# CheetahBooster.net
KiCad netlist of a schematic drawn in EAGLE
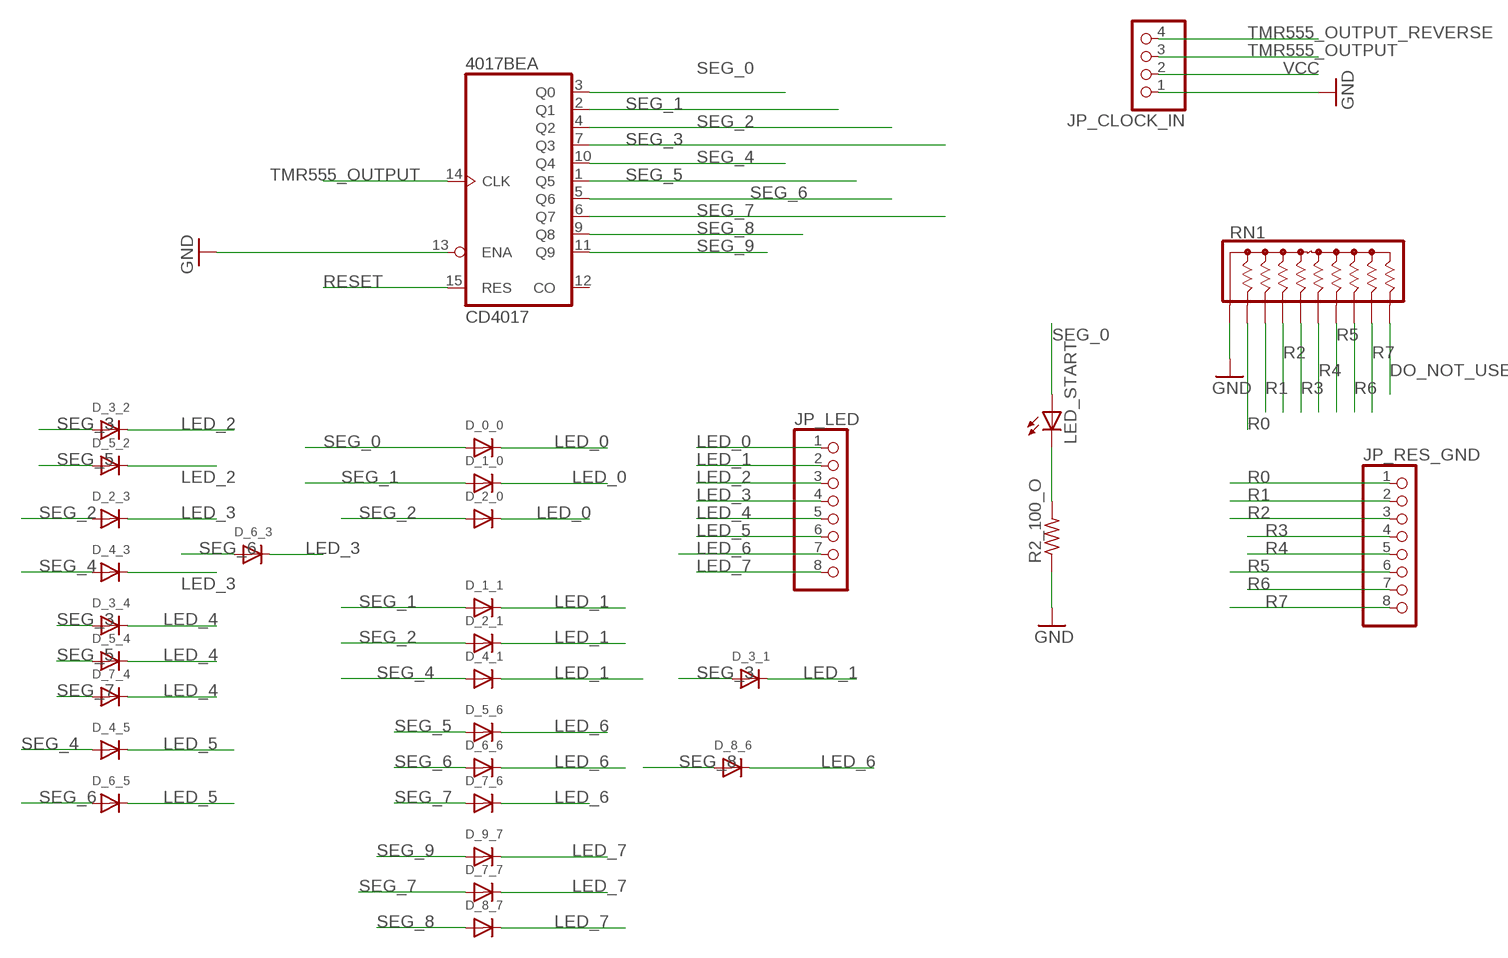
[diagram p0: schematic, sheet 1]

(export (version "E")
  (design (tool "Eeschema 10.0.6"))
  (components
    (comp (ref "4017BE")
      (value "CD4017")
      (footprint "eagle-import:DIL16")
      (libsource (lib "eagle-import") (part "CD4017"))
    )
    (comp (ref "D_0_0")
      (value "DIODESMA")
      (footprint "eagle-import:SMADIODE")
      (libsource (lib "eagle-import") (part "DIODESMA"))
    )
    (comp (ref "D_1_0")
      (value "DIODESMA")
      (footprint "eagle-import:SMADIODE")
      (libsource (lib "eagle-import") (part "DIODESMA"))
    )
    (comp (ref "D_1_1")
      (value "DIODESMA")
      (footprint "eagle-import:SMADIODE")
      (libsource (lib "eagle-import") (part "DIODESMA"))
    )
    (comp (ref "D_2_0")
      (value "DIODESMA")
      (footprint "eagle-import:SMADIODE")
      (libsource (lib "eagle-import") (part "DIODESMA"))
    )
    (comp (ref "D_2_1")
      (value "DIODESMA")
      (footprint "eagle-import:SMADIODE")
      (libsource (lib "eagle-import") (part "DIODESMA"))
    )
    (comp (ref "D_2_3")
      (value "DIODESMA")
      (footprint "eagle-import:SMADIODE")
      (libsource (lib "eagle-import") (part "DIODESMA"))
    )
    (comp (ref "D_3_1")
      (value "DIODESMA")
      (footprint "eagle-import:SMADIODE")
      (libsource (lib "eagle-import") (part "DIODESMA"))
    )
    (comp (ref "D_3_2")
      (value "DIODESMA")
      (footprint "eagle-import:SMADIODE")
      (libsource (lib "eagle-import") (part "DIODESMA"))
    )
    (comp (ref "D_3_4")
      (value "DIODESMA")
      (footprint "eagle-import:SMADIODE")
      (libsource (lib "eagle-import") (part "DIODESMA"))
    )
    (comp (ref "D_4_1")
      (value "DIODESMA")
      (footprint "eagle-import:SMADIODE")
      (libsource (lib "eagle-import") (part "DIODESMA"))
    )
    (comp (ref "D_4_3")
      (value "DIODESMA")
      (footprint "eagle-import:SMADIODE")
      (libsource (lib "eagle-import") (part "DIODESMA"))
    )
    (comp (ref "D_4_5")
      (value "DIODESMA")
      (footprint "eagle-import:SMADIODE")
      (libsource (lib "eagle-import") (part "DIODESMA"))
    )
    (comp (ref "D_5_2")
      (value "DIODESMA")
      (footprint "eagle-import:SMADIODE")
      (libsource (lib "eagle-import") (part "DIODESMA"))
    )
    (comp (ref "D_5_4")
      (value "DIODESMA")
      (footprint "eagle-import:SMADIODE")
      (libsource (lib "eagle-import") (part "DIODESMA"))
    )
    (comp (ref "D_5_6")
      (value "DIODESMA")
      (footprint "eagle-import:SMADIODE")
      (libsource (lib "eagle-import") (part "DIODESMA"))
    )
    (comp (ref "D_6_3")
      (value "DIODESMA")
      (footprint "eagle-import:SMADIODE")
      (libsource (lib "eagle-import") (part "DIODESMA"))
    )
    (comp (ref "D_6_5")
      (value "DIODESMA")
      (footprint "eagle-import:SMADIODE")
      (libsource (lib "eagle-import") (part "DIODESMA"))
    )
    (comp (ref "D_6_6")
      (value "DIODESMA")
      (footprint "eagle-import:SMADIODE")
      (libsource (lib "eagle-import") (part "DIODESMA"))
    )
    (comp (ref "D_7_4")
      (value "DIODESMA")
      (footprint "eagle-import:SMADIODE")
      (libsource (lib "eagle-import") (part "DIODESMA"))
    )
    (comp (ref "D_7_6")
      (value "DIODESMA")
      (footprint "eagle-import:SMADIODE")
      (libsource (lib "eagle-import") (part "DIODESMA"))
    )
    (comp (ref "D_7_7")
      (value "DIODESMA")
      (footprint "eagle-import:SMADIODE")
      (libsource (lib "eagle-import") (part "DIODESMA"))
    )
    (comp (ref "D_8_6")
      (value "DIODESMA")
      (footprint "eagle-import:SMADIODE")
      (libsource (lib "eagle-import") (part "DIODESMA"))
    )
    (comp (ref "D_8_7")
      (value "DIODESMA")
      (footprint "eagle-import:SMADIODE")
      (libsource (lib "eagle-import") (part "DIODESMA"))
    )
    (comp (ref "D_9_7")
      (value "DIODESMA")
      (footprint "eagle-import:SMADIODE")
      (libsource (lib "eagle-import") (part "DIODESMA"))
    )
    (comp (ref "JP_CLOCK_IN")
      (value "PINHD-1X4")
      (footprint "eagle-import:1X04")
      (libsource (lib "eagle-import") (part "PINHD-1X4"))
    )
    (comp (ref "JP_LED")
      (value "PINHD-1X8")
      (footprint "eagle-import:1X08")
      (libsource (lib "eagle-import") (part "PINHD-1X8"))
    )
    (comp (ref "JP_RES_GND")
      (value "PINHD-1X8")
      (footprint "eagle-import:1X08")
      (libsource (lib "eagle-import") (part "PINHD-1X8"))
    )
    (comp (ref "LED_START")
      (value "LEDSMT1206")
      (footprint "eagle-import:1206")
      (libsource (lib "eagle-import") (part "LEDSMT1206"))
    )
    (comp (ref "R2_100_O")
      (value "R-US_R1206")
      (footprint "eagle-import:R1206")
      (libsource (lib "eagle-import") (part "R-US_R1206"))
    )
    (comp (ref "RN1")
      (value "4610X")
      (footprint "eagle-import:SIP10")
      (libsource (lib "eagle-import") (part "4610X"))
    )
  )
  (nets
    (net (code "1") (name "/DO_NOT_USE") (class "Default")
      (node (ref "RN1") (pin "10") (pinfunction "10_10") (pintype "passive"))
    )
    (net (code "2") (name "/LED_0") (class "Default")
      (node (ref "D_0_0") (pin "C") (pinfunction "C_C") (pintype "passive"))
      (node (ref "D_1_0") (pin "C") (pinfunction "C_C") (pintype "passive"))
      (node (ref "D_2_0") (pin "C") (pinfunction "C_C") (pintype "passive"))
      (node (ref "JP_LED") (pin "1") (pinfunction "1_1") (pintype "passive"))
    )
    (net (code "3") (name "/LED_1") (class "Default")
      (node (ref "D_1_1") (pin "C") (pinfunction "C_C") (pintype "passive"))
      (node (ref "D_2_1") (pin "C") (pinfunction "C_C") (pintype "passive"))
      (node (ref "D_3_1") (pin "C") (pinfunction "C_C") (pintype "passive"))
      (node (ref "D_4_1") (pin "C") (pinfunction "C_C") (pintype "passive"))
      (node (ref "JP_LED") (pin "2") (pinfunction "2_2") (pintype "passive"))
    )
    (net (code "4") (name "/LED_2") (class "Default")
      (node (ref "D_3_2") (pin "C") (pinfunction "C_C") (pintype "passive"))
      (node (ref "D_5_2") (pin "C") (pinfunction "C_C") (pintype "passive"))
      (node (ref "JP_LED") (pin "3") (pinfunction "3_3") (pintype "passive"))
    )
    (net (code "5") (name "/LED_3") (class "Default")
      (node (ref "D_2_3") (pin "C") (pinfunction "C_C") (pintype "passive"))
      (node (ref "D_4_3") (pin "C") (pinfunction "C_C") (pintype "passive"))
      (node (ref "D_6_3") (pin "C") (pinfunction "C_C") (pintype "passive"))
      (node (ref "JP_LED") (pin "4") (pinfunction "4_4") (pintype "passive"))
    )
    (net (code "6") (name "/LED_4") (class "Default")
      (node (ref "D_3_4") (pin "C") (pinfunction "C_C") (pintype "passive"))
      (node (ref "D_5_4") (pin "C") (pinfunction "C_C") (pintype "passive"))
      (node (ref "D_7_4") (pin "C") (pinfunction "C_C") (pintype "passive"))
      (node (ref "JP_LED") (pin "5") (pinfunction "5_5") (pintype "passive"))
    )
    (net (code "7") (name "/LED_5") (class "Default")
      (node (ref "D_4_5") (pin "C") (pinfunction "C_C") (pintype "passive"))
      (node (ref "D_6_5") (pin "C") (pinfunction "C_C") (pintype "passive"))
      (node (ref "JP_LED") (pin "6") (pinfunction "6_6") (pintype "passive"))
    )
    (net (code "8") (name "/LED_6") (class "Default")
      (node (ref "D_5_6") (pin "C") (pinfunction "C_C") (pintype "passive"))
      (node (ref "D_6_6") (pin "C") (pinfunction "C_C") (pintype "passive"))
      (node (ref "D_7_6") (pin "C") (pinfunction "C_C") (pintype "passive"))
      (node (ref "D_8_6") (pin "C") (pinfunction "C_C") (pintype "passive"))
      (node (ref "JP_LED") (pin "7") (pinfunction "7_7") (pintype "passive"))
    )
    (net (code "9") (name "/LED_7") (class "Default")
      (node (ref "D_7_7") (pin "C") (pinfunction "C_C") (pintype "passive"))
      (node (ref "D_8_7") (pin "C") (pinfunction "C_C") (pintype "passive"))
      (node (ref "D_9_7") (pin "C") (pinfunction "C_C") (pintype "passive"))
      (node (ref "JP_LED") (pin "8") (pinfunction "8_8") (pintype "passive"))
    )
    (net (code "10") (name "/R0") (class "Default")
      (node (ref "JP_RES_GND") (pin "1") (pinfunction "1_1") (pintype "passive"))
      (node (ref "RN1") (pin "2") (pinfunction "2_2") (pintype "passive"))
    )
    (net (code "11") (name "/R1") (class "Default")
      (node (ref "JP_RES_GND") (pin "2") (pinfunction "2_2") (pintype "passive"))
      (node (ref "RN1") (pin "3") (pinfunction "3_3") (pintype "passive"))
    )
    (net (code "12") (name "/R2") (class "Default")
      (node (ref "JP_RES_GND") (pin "3") (pinfunction "3_3") (pintype "passive"))
      (node (ref "RN1") (pin "4") (pinfunction "4_4") (pintype "passive"))
    )
    (net (code "13") (name "/R3") (class "Default")
      (node (ref "JP_RES_GND") (pin "4") (pinfunction "4_4") (pintype "passive"))
      (node (ref "RN1") (pin "5") (pinfunction "5_5") (pintype "passive"))
    )
    (net (code "14") (name "/R4") (class "Default")
      (node (ref "JP_RES_GND") (pin "5") (pinfunction "5_5") (pintype "passive"))
      (node (ref "RN1") (pin "6") (pinfunction "6_6") (pintype "passive"))
    )
    (net (code "15") (name "/R5") (class "Default")
      (node (ref "JP_RES_GND") (pin "6") (pinfunction "6_6") (pintype "passive"))
      (node (ref "RN1") (pin "7") (pinfunction "7_7") (pintype "passive"))
    )
    (net (code "16") (name "/R6") (class "Default")
      (node (ref "JP_RES_GND") (pin "7") (pinfunction "7_7") (pintype "passive"))
      (node (ref "RN1") (pin "8") (pinfunction "8_8") (pintype "passive"))
    )
    (net (code "17") (name "/R7") (class "Default")
      (node (ref "JP_RES_GND") (pin "8") (pinfunction "8_8") (pintype "passive"))
      (node (ref "RN1") (pin "9") (pinfunction "9_9") (pintype "passive"))
    )
    (net (code "18") (name "/RESET") (class "Default")
      (node (ref "4017BE") (pin "15") (pinfunction "RES_15") (pintype "input"))
    )
    (net (code "19") (name "/SEG_0") (class "Default")
      (node (ref "4017BE") (pin "3") (pinfunction "Q0_3") (pintype "output"))
      (node (ref "D_0_0") (pin "A") (pinfunction "A_A") (pintype "passive"))
      (node (ref "LED_START") (pin "A") (pinfunction "A_A") (pintype "passive"))
    )
    (net (code "20") (name "/SEG_1") (class "Default")
      (node (ref "4017BE") (pin "2") (pinfunction "Q1_2") (pintype "output"))
      (node (ref "D_1_0") (pin "A") (pinfunction "A_A") (pintype "passive"))
      (node (ref "D_1_1") (pin "A") (pinfunction "A_A") (pintype "passive"))
    )
    (net (code "21") (name "/SEG_2") (class "Default")
      (node (ref "4017BE") (pin "4") (pinfunction "Q2_4") (pintype "output"))
      (node (ref "D_2_0") (pin "A") (pinfunction "A_A") (pintype "passive"))
      (node (ref "D_2_1") (pin "A") (pinfunction "A_A") (pintype "passive"))
      (node (ref "D_2_3") (pin "A") (pinfunction "A_A") (pintype "passive"))
    )
    (net (code "22") (name "/SEG_3") (class "Default")
      (node (ref "4017BE") (pin "7") (pinfunction "Q3_7") (pintype "output"))
      (node (ref "D_3_1") (pin "A") (pinfunction "A_A") (pintype "passive"))
      (node (ref "D_3_2") (pin "A") (pinfunction "A_A") (pintype "passive"))
      (node (ref "D_3_4") (pin "A") (pinfunction "A_A") (pintype "passive"))
    )
    (net (code "23") (name "/SEG_4") (class "Default")
      (node (ref "4017BE") (pin "10") (pinfunction "Q4_10") (pintype "output"))
      (node (ref "D_4_1") (pin "A") (pinfunction "A_A") (pintype "passive"))
      (node (ref "D_4_3") (pin "A") (pinfunction "A_A") (pintype "passive"))
      (node (ref "D_4_5") (pin "A") (pinfunction "A_A") (pintype "passive"))
    )
    (net (code "24") (name "/SEG_5") (class "Default")
      (node (ref "4017BE") (pin "1") (pinfunction "Q5_1") (pintype "output"))
      (node (ref "D_5_2") (pin "A") (pinfunction "A_A") (pintype "passive"))
      (node (ref "D_5_4") (pin "A") (pinfunction "A_A") (pintype "passive"))
      (node (ref "D_5_6") (pin "A") (pinfunction "A_A") (pintype "passive"))
    )
    (net (code "25") (name "/SEG_6") (class "Default")
      (node (ref "4017BE") (pin "5") (pinfunction "Q6_5") (pintype "output"))
      (node (ref "D_6_3") (pin "A") (pinfunction "A_A") (pintype "passive"))
      (node (ref "D_6_5") (pin "A") (pinfunction "A_A") (pintype "passive"))
      (node (ref "D_6_6") (pin "A") (pinfunction "A_A") (pintype "passive"))
    )
    (net (code "26") (name "/SEG_7") (class "Default")
      (node (ref "4017BE") (pin "6") (pinfunction "Q7_6") (pintype "output"))
      (node (ref "D_7_4") (pin "A") (pinfunction "A_A") (pintype "passive"))
      (node (ref "D_7_6") (pin "A") (pinfunction "A_A") (pintype "passive"))
      (node (ref "D_7_7") (pin "A") (pinfunction "A_A") (pintype "passive"))
    )
    (net (code "27") (name "/SEG_8") (class "Default")
      (node (ref "4017BE") (pin "9") (pinfunction "Q8_9") (pintype "output"))
      (node (ref "D_8_6") (pin "A") (pinfunction "A_A") (pintype "passive"))
      (node (ref "D_8_7") (pin "A") (pinfunction "A_A") (pintype "passive"))
    )
    (net (code "28") (name "/SEG_9") (class "Default")
      (node (ref "4017BE") (pin "11") (pinfunction "Q9_11") (pintype "output"))
      (node (ref "D_9_7") (pin "A") (pinfunction "A_A") (pintype "passive"))
    )
    (net (code "29") (name "/TMR555_OUTPUT") (class "Default")
      (node (ref "4017BE") (pin "14") (pinfunction "CLK_14") (pintype "input"))
      (node (ref "JP_CLOCK_IN") (pin "3") (pinfunction "3_3") (pintype "passive"))
    )
    (net (code "30") (name "/TMR555_OUTPUT_REVERSE") (class "Default")
      (node (ref "JP_CLOCK_IN") (pin "4") (pinfunction "4_4") (pintype "passive"))
    )
    (net (code "31") (name "/VCC") (class "Default")
      (node (ref "JP_CLOCK_IN") (pin "2") (pinfunction "2_2") (pintype "passive"))
    )
    (net (code "32") (name "GND") (class "Default")
      (node (ref "4017BE") (pin "13") (pinfunction "ENA_13") (pintype "input"))
      (node (ref "JP_CLOCK_IN") (pin "1") (pinfunction "1_1") (pintype "passive"))
      (node (ref "R2_100_O") (pin "1") (pinfunction "1_1") (pintype "passive"))
      (node (ref "RN1") (pin "1") (pinfunction "1_1") (pintype "passive"))
    )
    (net (code "33") (name "Net-(LED_START-PadC)") (class "Default")
      (node (ref "LED_START") (pin "C") (pinfunction "C_C") (pintype "passive"))
      (node (ref "R2_100_O") (pin "2") (pinfunction "2_2") (pintype "passive"))
    )
    (net (code "34") (name "unconnected-(4017BEA-CO-Pad12)") (class "Default")
      (node (ref "4017BE") (pin "12") (pinfunction "CO_12") (pintype "output"))
    )
  )
)
